# TDA2003-Amplifier-2.net
KiCad netlist of a schematic drawn in EAGLE
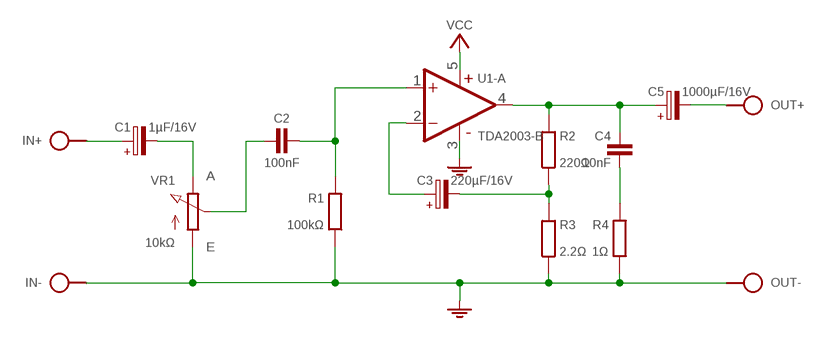
[diagram p0: schematic, sheet 1]

(export (version "E")
  (design (tool "Eeschema 10.0.6"))
  (components
    (comp (ref "C1")
      (value "1µF/16V")
      (footprint "eagle-import:E2,5-4")
      (libsource (lib "eagle-import") (part "CPOL-HE2,5-4"))
    )
    (comp (ref "C2")
      (value "100nF")
      (footprint "eagle-import:C050-020X044_V")
      (libsource (lib "eagle-import") (part "C-H050-020X044/V"))
    )
    (comp (ref "C3")
      (value "220µF/16V")
      (footprint "eagle-import:E5-5")
      (libsource (lib "eagle-import") (part "CPOL-HE5-5"))
    )
    (comp (ref "C4")
      (value "10nF")
      (footprint "eagle-import:C050-025X075_V")
      (libsource (lib "eagle-import") (part "C050-025X075/V"))
    )
    (comp (ref "C5")
      (value "1000µF/16V")
      (footprint "eagle-import:E5-5")
      (libsource (lib "eagle-import") (part "CPOL-HE5-5"))
    )
    (comp (ref "IN")
      (value "SPAD+--+")
      (footprint "eagle-import:SPAD-+")
      (libsource (lib "eagle-import") (part "SPAD+--+"))
    )
    (comp (ref "OUT")
      (value "SPAD+-+-")
      (footprint "eagle-import:SPAD+-")
      (libsource (lib "eagle-import") (part "SPAD+-+-"))
    )
    (comp (ref "PWR")
      (value "VCC_GNDL")
      (footprint "eagle-import:SPAD-+")
      (libsource (lib "eagle-import") (part "VCC_GNDL"))
    )
    (comp (ref "R1")
      (value "100kΩ")
      (footprint "eagle-import:0204_10-V")
      (libsource (lib "eagle-import") (part "R0204/10-V"))
    )
    (comp (ref "R2")
      (value "220Ω")
      (footprint "eagle-import:0204_10-V")
      (libsource (lib "eagle-import") (part "R0204/10-V"))
    )
    (comp (ref "R3")
      (value "2.2Ω")
      (footprint "eagle-import:0204_10-V")
      (libsource (lib "eagle-import") (part "R0204/10-V"))
    )
    (comp (ref "R4")
      (value "1Ω")
      (footprint "eagle-import:0204_10-V")
      (libsource (lib "eagle-import") (part "R0204/10-V"))
    )
    (comp (ref "U1")
      (value "TDA2003-B")
      (footprint "eagle-import:TO220-B5")
      (libsource (lib "eagle-import") (part "TDA2003-B"))
    )
    (comp (ref "VR1")
      (value "10kΩ")
      (footprint "eagle-import:CONN-3P")
      (libsource (lib "eagle-import") (part "POT-3P"))
    )
  )
  (nets
    (net (code "1") (name "GND") (class "Default")
      (node (ref "IN") (pin "1") (pinfunction "P$1_1") (pintype "passive"))
      (node (ref "OUT") (pin "1") (pinfunction "P$1_1") (pintype "passive"))
      (node (ref "PWR") (pin "1") (pinfunction "GND_1") (pintype "power_in"))
      (node (ref "R1") (pin "2") (pinfunction "1_2") (pintype "passive"))
      (node (ref "R3") (pin "2") (pinfunction "1_2") (pintype "passive"))
      (node (ref "R4") (pin "2") (pinfunction "1_2") (pintype "passive"))
      (node (ref "U1") (pin "3") (pinfunction "V-_3") (pintype "power_in"))
      (node (ref "VR1") (pin "1") (pinfunction "A_1") (pintype "passive"))
    )
    (net (code "2") (name "Net-(INA-P$1)") (class "Default")
      (node (ref "C1") (pin "+") (pinfunction "+_+") (pintype "passive"))
      (node (ref "IN") (pin "2") (pinfunction "P$1_2") (pintype "passive"))
    )
    (net (code "3") (name "Net-(OUTA-P$1)") (class "Default")
      (node (ref "C5") (pin "-") (pinfunction "-_-") (pintype "passive"))
      (node (ref "OUT") (pin "2") (pinfunction "P$1_2") (pintype "passive"))
    )
    (net (code "4") (name "Net-(PWRA-VCC)") (class "Default")
      (node (ref "PWR") (pin "2") (pinfunction "VCC_2") (pintype "power_in"))
      (node (ref "U1") (pin "5") (pinfunction "V+_5") (pintype "power_in"))
    )
    (net (code "5") (name "Net-(R1-2)") (class "Default")
      (node (ref "C2") (pin "2") (pinfunction "2_2") (pintype "passive"))
      (node (ref "R1") (pin "1") (pinfunction "2_1") (pintype "passive"))
      (node (ref "U1") (pin "1") (pinfunction "+IN_1") (pintype "input"))
    )
    (net (code "6") (name "Net-(R2-1)") (class "Default")
      (node (ref "C3") (pin "-") (pinfunction "-_-") (pintype "passive"))
      (node (ref "R2") (pin "2") (pinfunction "1_2") (pintype "passive"))
      (node (ref "R3") (pin "1") (pinfunction "2_1") (pintype "passive"))
    )
    (net (code "7") (name "Net-(R2-2)") (class "Default")
      (node (ref "C4") (pin "1") (pinfunction "1_1") (pintype "passive"))
      (node (ref "C5") (pin "+") (pinfunction "+_+") (pintype "passive"))
      (node (ref "R2") (pin "1") (pinfunction "2_1") (pintype "passive"))
      (node (ref "U1") (pin "4") (pinfunction "OUT_4") (pintype "output"))
    )
    (net (code "8") (name "Net-(R4-2)") (class "Default")
      (node (ref "C4") (pin "2") (pinfunction "2_2") (pintype "passive"))
      (node (ref "R4") (pin "1") (pinfunction "2_1") (pintype "passive"))
    )
    (net (code "9") (name "Net-(U1A--IN)") (class "Default")
      (node (ref "C3") (pin "+") (pinfunction "+_+") (pintype "passive"))
      (node (ref "U1") (pin "2") (pinfunction "-IN_2") (pintype "input"))
    )
    (net (code "10") (name "Net-(VR1-E)") (class "Default")
      (node (ref "C1") (pin "-") (pinfunction "-_-") (pintype "passive"))
      (node (ref "VR1") (pin "3") (pinfunction "E_3") (pintype "passive"))
    )
    (net (code "11") (name "Net-(VR1-S)") (class "Default")
      (node (ref "C2") (pin "1") (pinfunction "1_1") (pintype "passive"))
      (node (ref "VR1") (pin "2") (pinfunction "S_2") (pintype "passive"))
    )
  )
)
